# Energy_Harvesting.net
KiCad netlist of a schematic drawn in Altium Designer
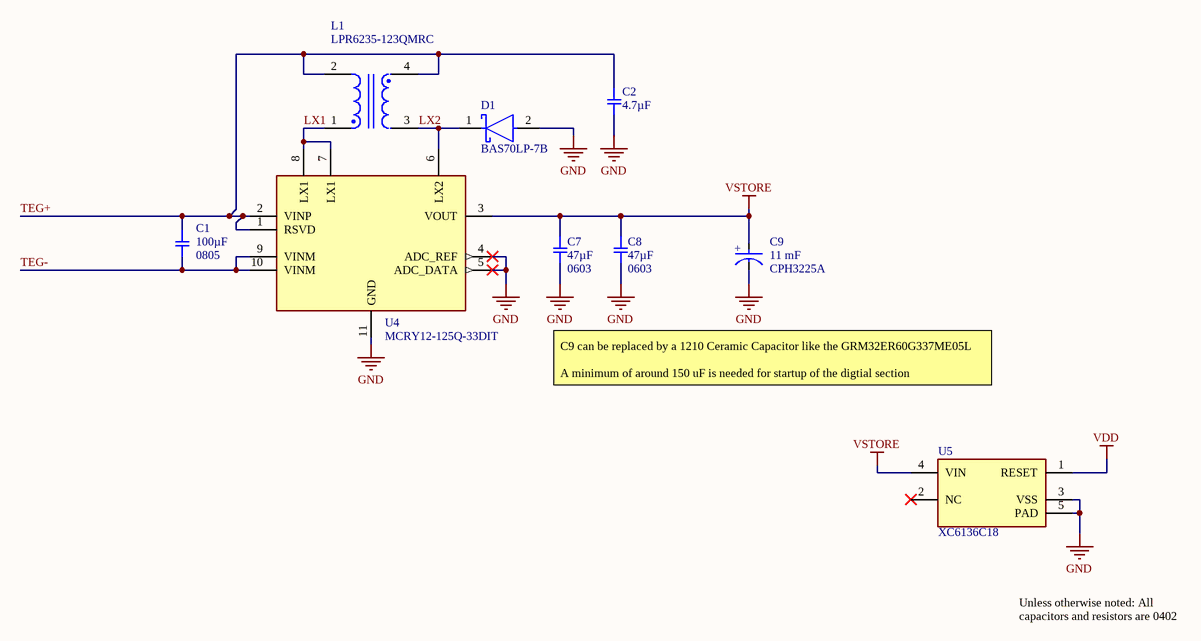
[diagram p0: Energy Harvesting.SchDoc]

(export (version "E")
  (design (tool "Eeschema 10.0.6"))
  (components
    (comp (ref "C1")
      (value "100µF")
      (footprint "CAPC2012X12N")
      (description "CAP CER 100UF 2.5V X6S 0805")
      (fields
        (field (name "DIGI-KEY PART NUMBER") "490-13977-1-ND")
        (field (name "PART NUMBER") "GRM21BC80E107ME15L")
        (field (name "PACKAGE / CASE") "0805")
      )
      (libsource (lib "capacitor_murata_0805") (part "GRM21BC80E107ME15L"))
    )
    (comp (ref "C2")
      (value "4.7µF")
      (footprint "RESC1005X03N")
      (description "CAP CER 4.7UF 6.3V X5R 0402")
      (fields
        (field (name "DIGI-KEY PART NUMBER") "490-5408-1-ND")
        (field (name "PART NUMBER") "GRM155R60J475ME87D")
      )
      (libsource (lib "capacitor_murata_0402") (part "GRM155R60J475ME87D"))
    )
    (comp (ref "C7")
      (value "47µF")
      (footprint "CAPC1608X12N")
      (description "CAP CER 47UF 6.3V X5R 0603")
      (fields
        (field (name "DIGI-KEY PART NUMBER") "490-13211-1-ND")
        (field (name "PART NUMBER") "GRJ155R60J106ME11D")
        (field (name "PACKAGE / CASE") "0603")
      )
      (libsource (lib "capacitor_murata_0402") (part "GRJ155R60J106ME11D"))
    )
    (comp (ref "C8")
      (value "47µF")
      (footprint "CAPC1608X12N")
      (description "CAP CER 47UF 6.3V X5R 0603")
      (fields
        (field (name "DIGI-KEY PART NUMBER") "490-13211-1-ND")
        (field (name "PART NUMBER") "GRJ155R60J106ME11D")
        (field (name "PACKAGE / CASE") "0603")
      )
      (libsource (lib "capacitor_murata_0402") (part "GRJ155R60J106ME11D"))
    )
    (comp (ref "C9")
      (value "CPH3225A")
      (footprint "CPH3225A")
      (description "Supercapacitors / Ultracapacitors Reflow EDLC 3.3V, 11mF, 160 Ohm")
      (fields (field (name "CAPACITY") "11 mF"))
      (libsource (lib "Library") (part "CPH3225A"))
    )
    (comp (ref "D1")
      (value "BAS70LP-7B")
      (footprint "FP-X1-DFN1006-2-MFG")
      (description "DIODE SCHTTKY 70V 70MA X1DFN1006")
      (fields
        (field (name "MANUFACTURER") "Diodes Inc.")
        (field (name "OCTOPART") "https://octopart.com/bas70lp-7b-diodes+inc.-22053921")
      )
      (libsource (lib "Altium Content Vault") (part "1d6ec82d83fb6aee721767c19dac4b9"))
    )
    (comp (ref "L1")
      (value "LPR6235-123QMRC")
      (footprint "LPR6235")
      (description "Gekoppelde smoorspoelen 12.5uH 12% 900mA 200 Ohms")
      (libsource (lib "Library") (part "LPR6235-123QMRC"))
    )
    (comp (ref "U4")
      (value "MCRY12-125Q-33DIT")
      (footprint "10DFN")
      (libsource (lib "Library") (part "MCRY12"))
    )
    (comp (ref "U5")
      (value "XC6136C18")
      (footprint "USPQ-4B05")
      (description "Controlecircuits Ultra-Low Power (88nA) Voltage Detector")
      (libsource (lib "Library") (part "XC6136N18A9R-G"))
    )
  )
  (nets
    (net (code "1") (name "/LX1") (class "Default")
      (node (ref "L1") (pin "1") (pinfunction "1_1") (pintype "passive"))
      (node (ref "U4") (pin "7") (pinfunction "LX1_7") (pintype "power_in"))
      (node (ref "U4") (pin "8") (pinfunction "LX1_8") (pintype "power_in"))
    )
    (net (code "2") (name "/LX2") (class "Default")
      (node (ref "D1") (pin "1") (pinfunction "C_1") (pintype "passive"))
      (node (ref "L1") (pin "3") (pinfunction "3_3") (pintype "passive"))
      (node (ref "U4") (pin "6") (pinfunction "LX2_6") (pintype "power_in"))
    )
    (net (code "3") (name "/TEG+") (class "Default")
      (node (ref "C1") (pin "1") (pinfunction "1_1") (pintype "passive"))
      (node (ref "C2") (pin "1") (pinfunction "1_1") (pintype "passive"))
      (node (ref "L1") (pin "2") (pinfunction "2_2") (pintype "passive"))
      (node (ref "L1") (pin "4") (pinfunction "4_4") (pintype "passive"))
      (node (ref "U4") (pin "1") (pinfunction "RSVD_1") (pintype "power_in"))
      (node (ref "U4") (pin "2") (pinfunction "VINP_2") (pintype "power_in"))
    )
    (net (code "4") (name "/TEG-") (class "Default")
      (node (ref "C1") (pin "2") (pinfunction "2_2") (pintype "passive"))
      (node (ref "U4") (pin "10") (pinfunction "VINM_10") (pintype "power_in"))
      (node (ref "U4") (pin "9") (pinfunction "VINM_9") (pintype "power_in"))
    )
    (net (code "5") (name "GND") (class "Default")
      (node (ref "C2") (pin "2") (pinfunction "2_2") (pintype "passive"))
      (node (ref "C7") (pin "2") (pinfunction "2_2") (pintype "passive"))
      (node (ref "C8") (pin "2") (pinfunction "2_2") (pintype "passive"))
      (node (ref "C9") (pin "2") (pinfunction "A_2") (pintype "passive"))
      (node (ref "D1") (pin "2") (pinfunction "A_2") (pintype "passive"))
      (node (ref "U4") (pin "11") (pinfunction "GND_11") (pintype "power_in"))
      (node (ref "U4") (pin "4") (pinfunction "ADC_REF_4") (pintype "output"))
      (node (ref "U4") (pin "5") (pinfunction "ADC_DATA_5") (pintype "output"))
      (node (ref "U5") (pin "3") (pinfunction "VSS_3") (pintype "power_in"))
      (node (ref "U5") (pin "5") (pinfunction "PAD_5") (pintype "power_in"))
    )
    (net (code "6") (name "VDD") (class "Default")
      (node (ref "U5") (pin "1") (pinfunction "RESET_1") (pintype "power_in"))
    )
    (net (code "7") (name "VSTORE") (class "Default")
      (node (ref "C7") (pin "1") (pinfunction "1_1") (pintype "passive"))
      (node (ref "C8") (pin "1") (pinfunction "1_1") (pintype "passive"))
      (node (ref "C9") (pin "1") (pinfunction "C_1") (pintype "passive"))
      (node (ref "U4") (pin "3") (pinfunction "VOUT_3") (pintype "power_in"))
      (node (ref "U5") (pin "4") (pinfunction "VIN_4") (pintype "power_in"))
    )
    (net (code "8") (name "unconnected-(U5-NC-Pad2)") (class "Default")
      (node (ref "U5") (pin "2") (pinfunction "NC_2") (pintype "power_in+no_connect"))
    )
  )
)
